# Connector_2.net
KiCad netlist of a schematic drawn in Altium Designer
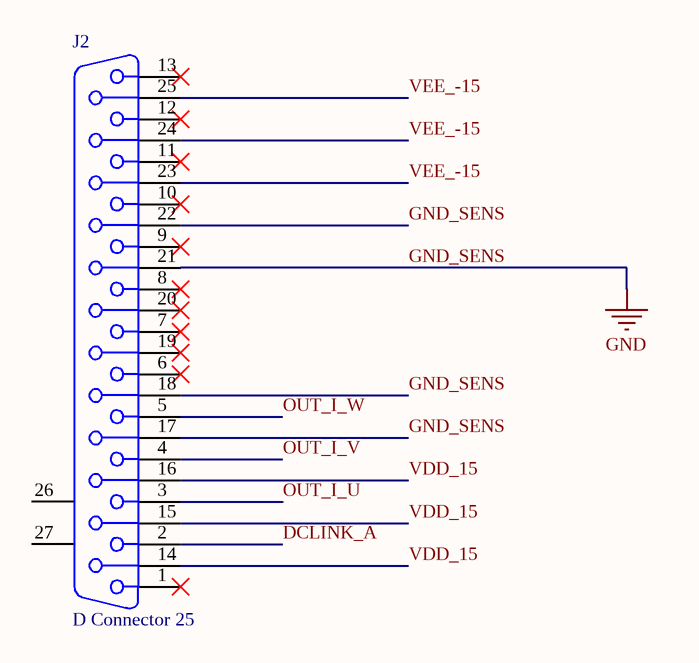
[diagram p0: Connector 2.SchDoc]

(export (version "E")
  (design (tool "Eeschema 10.0.6"))
  (components
    (comp (ref "J2")
      (value "D Connector 25")
      (footprint "DSUB1.385-2H25A")
      (description "Receptacle Assembly, 25 Position, Right Angle")
      (fields (field (name "PUBLISHER") "Altium Limited"))
      (libsource (lib "Miscellaneous Connectors") (part "D Connector 25"))
    )
  )
  (nets
    (net (code "1") (name "/DCLINK_A") (class "Default")
      (node (ref "J2") (pin "2") (pinfunction "2_2") (pintype "passive"))
    )
    (net (code "2") (name "/OUT_I_U") (class "Default")
      (node (ref "J2") (pin "3") (pinfunction "3_3") (pintype "passive"))
    )
    (net (code "3") (name "/OUT_I_V") (class "Default")
      (node (ref "J2") (pin "4") (pinfunction "4_4") (pintype "passive"))
    )
    (net (code "4") (name "/OUT_I_W") (class "Default")
      (node (ref "J2") (pin "5") (pinfunction "5_5") (pintype "passive"))
    )
    (net (code "5") (name "/VDD_15") (class "Default")
      (node (ref "J2") (pin "14") (pinfunction "14_14") (pintype "passive"))
      (node (ref "J2") (pin "15") (pinfunction "15_15") (pintype "passive"))
      (node (ref "J2") (pin "16") (pinfunction "16_16") (pintype "passive"))
    )
    (net (code "6") (name "/VEE_-15") (class "Default")
      (node (ref "J2") (pin "23") (pinfunction "23_23") (pintype "passive"))
      (node (ref "J2") (pin "24") (pinfunction "24_24") (pintype "passive"))
      (node (ref "J2") (pin "25") (pinfunction "25_25") (pintype "passive"))
    )
    (net (code "7") (name "GND") (class "Default")
      (node (ref "J2") (pin "17") (pinfunction "17_17") (pintype "passive"))
      (node (ref "J2") (pin "18") (pinfunction "18_18") (pintype "passive"))
      (node (ref "J2") (pin "21") (pinfunction "21_21") (pintype "passive"))
      (node (ref "J2") (pin "22") (pinfunction "22_22") (pintype "passive"))
    )
    (net (code "8") (name "unconnected-(J2-MH1-Pad26)") (class "Default")
      (node (ref "J2") (pin "26") (pinfunction "MH1_26") (pintype "passive"))
    )
    (net (code "9") (name "unconnected-(J2-MH2-Pad27)") (class "Default")
      (node (ref "J2") (pin "27") (pinfunction "MH2_27") (pintype "passive"))
    )
    (net (code "10") (name "unconnected-(J2-Pad1)") (class "Default")
      (node (ref "J2") (pin "1") (pinfunction "1_1") (pintype "passive+no_connect"))
    )
    (net (code "11") (name "unconnected-(J2-Pad6)") (class "Default")
      (node (ref "J2") (pin "6") (pinfunction "6_6") (pintype "passive+no_connect"))
    )
    (net (code "12") (name "unconnected-(J2-Pad7)") (class "Default")
      (node (ref "J2") (pin "7") (pinfunction "7_7") (pintype "passive+no_connect"))
    )
    (net (code "13") (name "unconnected-(J2-Pad8)") (class "Default")
      (node (ref "J2") (pin "8") (pinfunction "8_8") (pintype "passive+no_connect"))
    )
    (net (code "14") (name "unconnected-(J2-Pad9)") (class "Default")
      (node (ref "J2") (pin "9") (pinfunction "9_9") (pintype "passive+no_connect"))
    )
    (net (code "15") (name "unconnected-(J2-Pad10)") (class "Default")
      (node (ref "J2") (pin "10") (pinfunction "10_10") (pintype "passive+no_connect"))
    )
    (net (code "16") (name "unconnected-(J2-Pad11)") (class "Default")
      (node (ref "J2") (pin "11") (pinfunction "11_11") (pintype "passive+no_connect"))
    )
    (net (code "17") (name "unconnected-(J2-Pad12)") (class "Default")
      (node (ref "J2") (pin "12") (pinfunction "12_12") (pintype "passive+no_connect"))
    )
    (net (code "18") (name "unconnected-(J2-Pad13)") (class "Default")
      (node (ref "J2") (pin "13") (pinfunction "13_13") (pintype "passive+no_connect"))
    )
    (net (code "19") (name "unconnected-(J2-Pad19)") (class "Default")
      (node (ref "J2") (pin "19") (pinfunction "19_19") (pintype "passive+no_connect"))
    )
    (net (code "20") (name "unconnected-(J2-Pad20)") (class "Default")
      (node (ref "J2") (pin "20") (pinfunction "20_20") (pintype "passive+no_connect"))
    )
  )
)
